# LinTempCont_indCh_proto.net
KiCad netlist of a schematic drawn in EAGLE
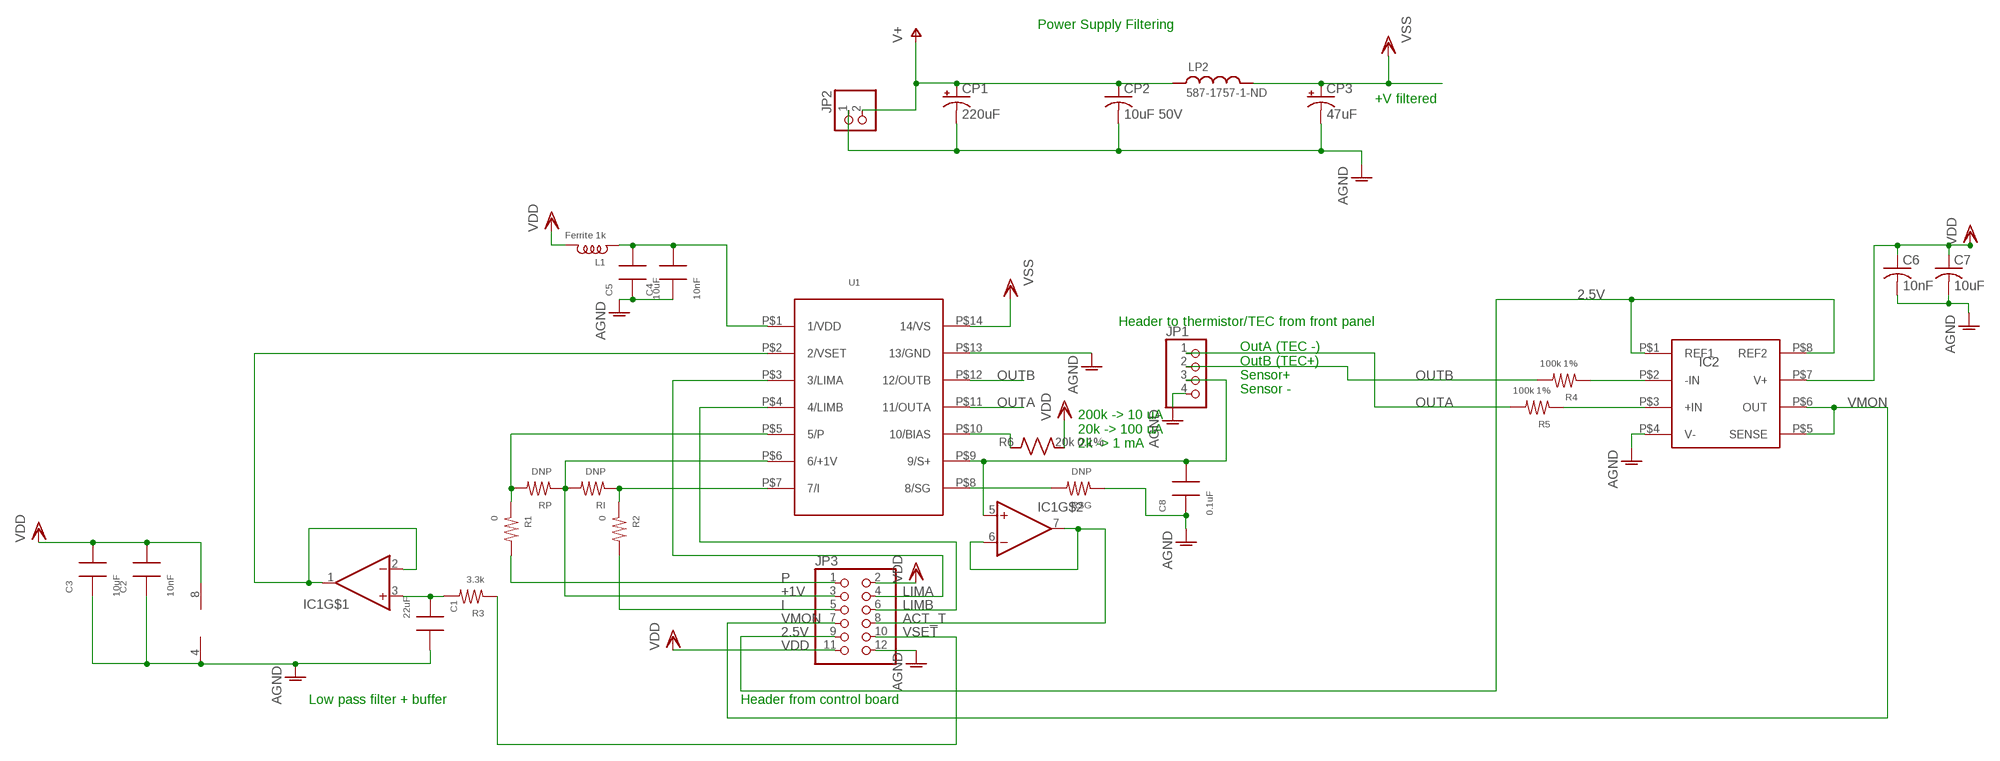
[diagram p0: schematic, sheet 1]

(export (version "E")
  (design (tool "Eeschema 10.0.6"))
  (components
    (comp (ref "C1")
      (value "22uF")
      (footprint "eagle-import:0805")
      (libsource (lib "eagle-import") (part "CAP0805"))
    )
    (comp (ref "C2")
      (value "10nF")
      (footprint "eagle-import:0603")
      (libsource (lib "eagle-import") (part "CAP0603"))
    )
    (comp (ref "C3")
      (value "10uF")
      (footprint "eagle-import:0805")
      (libsource (lib "eagle-import") (part "CAP0805"))
    )
    (comp (ref "C4")
      (value "10nF")
      (footprint "eagle-import:0805")
      (libsource (lib "eagle-import") (part "CAP0805"))
    )
    (comp (ref "C5")
      (value "10uF")
      (footprint "eagle-import:0603")
      (libsource (lib "eagle-import") (part "CAP0603"))
    )
    (comp (ref "C6")
      (value "10nF")
      (footprint "eagle-import:C0603")
      (libsource (lib "eagle-import") (part "C-USC0603"))
    )
    (comp (ref "C7")
      (value "10uF")
      (footprint "eagle-import:C0805")
      (libsource (lib "eagle-import") (part "C-USC0805"))
    )
    (comp (ref "C8")
      (value "0.1uF")
      (footprint "eagle-import:0603")
      (libsource (lib "eagle-import") (part "CAP0603"))
    )
    (comp (ref "CP1")
      (value "220uF")
      (footprint "eagle-import:PANASONIC_F")
      (libsource (lib "eagle-import") (part "CPOL-USF"))
    )
    (comp (ref "CP2")
      (value "10uF 50V")
      (footprint "eagle-import:C1206")
      (libsource (lib "eagle-import") (part "C-USC1206"))
    )
    (comp (ref "CP3")
      (value "47uF")
      (footprint "eagle-import:CT7343")
      (libsource (lib "eagle-import") (part "CPOL-USCT7343"))
    )
    (comp (ref "IC1")
      (value "OP727")
      (footprint "eagle-import:TSSOP8")
      (libsource (lib "eagle-import") (part "OP727"))
    )
    (comp (ref "IC2")
      (value "INA159")
      (footprint "eagle-import:VSSOP8")
      (libsource (lib "eagle-import") (part "INA159"))
    )
    (comp (ref "JP1")
      (value "SCRWTRM-1X4/90_ED550")
      (footprint "eagle-import:1X04_RA_SCRWTRM_ED550")
      (libsource (lib "eagle-import") (part "SCRWTRM-1X4/90_ED550"))
    )
    (comp (ref "JP2")
      (value "SCRWTRM-1X2/90_ED550")
      (footprint "eagle-import:1X02_RA_SCRWTRM_ED550")
      (libsource (lib "eagle-import") (part "SCRWTRM-1X2/90_ED550"))
    )
    (comp (ref "JP3")
      (value "PINHD-2X6")
      (footprint "eagle-import:2X06")
      (libsource (lib "eagle-import") (part "PINHD-2X6"))
    )
    (comp (ref "L1")
      (value "Ferrite 1k")
      (footprint "eagle-import:0805")
      (libsource (lib "eagle-import") (part "INDUCTOR-0805"))
    )
    (comp (ref "LP2")
      (value "587-1757-1-ND")
      (footprint "eagle-import:L_FERRITE_1810")
      (libsource (lib "eagle-import") (part "L_FERRITE_SMD"))
    )
    (comp (ref "R1")
      (value "0")
      (footprint "eagle-import:0603")
      (libsource (lib "eagle-import") (part "RES0603"))
    )
    (comp (ref "R2")
      (value "0")
      (footprint "eagle-import:0603")
      (libsource (lib "eagle-import") (part "RES0603"))
    )
    (comp (ref "R3")
      (value "3.3k")
      (footprint "eagle-import:0603")
      (libsource (lib "eagle-import") (part "RES0603"))
    )
    (comp (ref "R4")
      (value "100k 1%")
      (footprint "eagle-import:0603")
      (libsource (lib "eagle-import") (part "RES0603"))
    )
    (comp (ref "R5")
      (value "100k 1%")
      (footprint "eagle-import:0603")
      (libsource (lib "eagle-import") (part "RES0603"))
    )
    (comp (ref "R6")
      (value "20k 0.1%")
      (footprint "eagle-import:R_0805")
      (libsource (lib "eagle-import") (part "R_SMDR0805"))
    )
    (comp (ref "RI")
      (value "DNP")
      (footprint "eagle-import:0603")
      (libsource (lib "eagle-import") (part "RES0603"))
    )
    (comp (ref "RP")
      (value "DNP")
      (footprint "eagle-import:0603")
      (libsource (lib "eagle-import") (part "RES0603"))
    )
    (comp (ref "RSG")
      (value "DNP")
      (footprint "eagle-import:0603")
      (libsource (lib "eagle-import") (part "RES0603"))
    )
    (comp (ref "U1")
      (value "WTC3243")
      (footprint "eagle-import:WTC3293")
      (libsource (lib "eagle-import") (part "WTC3243"))
    )
  )
  (nets
    (net (code "1") (name "/+1V") (class "Default")
      (node (ref "JP3") (pin "3") (pinfunction "3_3") (pintype "passive"))
      (node (ref "RI") (pin "2") (pinfunction "P$2_2") (pintype "passive"))
      (node (ref "RP") (pin "1") (pinfunction "P$1_1") (pintype "passive"))
      (node (ref "U1") (pin "P$6") (pinfunction "6/+1V_P$6") (pintype "bidirectional"))
    )
    (net (code "2") (name "/2.5V") (class "Default")
      (node (ref "IC2") (pin "P$1") (pinfunction "REF1_P$1") (pintype "bidirectional"))
      (node (ref "IC2") (pin "P$8") (pinfunction "REF2_P$8") (pintype "bidirectional"))
      (node (ref "JP3") (pin "9") (pinfunction "9_9") (pintype "passive"))
    )
    (net (code "3") (name "/ACT_T") (class "Default")
      (node (ref "IC1") (pin "6") (pinfunction "-IN_6") (pintype "input"))
      (node (ref "IC1") (pin "7") (pinfunction "OUT_7") (pintype "output"))
      (node (ref "JP3") (pin "8") (pinfunction "8_8") (pintype "passive"))
    )
    (net (code "4") (name "/I") (class "Default")
      (node (ref "JP3") (pin "5") (pinfunction "5_5") (pintype "passive"))
      (node (ref "R2") (pin "2") (pinfunction "P$2_2") (pintype "passive"))
    )
    (net (code "5") (name "/LIMA") (class "Default")
      (node (ref "JP3") (pin "4") (pinfunction "4_4") (pintype "passive"))
      (node (ref "U1") (pin "P$3") (pinfunction "3/LIMA_P$3") (pintype "bidirectional"))
    )
    (net (code "6") (name "/LIMB") (class "Default")
      (node (ref "JP3") (pin "6") (pinfunction "6_6") (pintype "passive"))
      (node (ref "U1") (pin "P$4") (pinfunction "4/LIMB_P$4") (pintype "bidirectional"))
    )
    (net (code "7") (name "/OUTA") (class "Default")
      (node (ref "JP1") (pin "1") (pinfunction "1_1") (pintype "passive"))
      (node (ref "R5") (pin "2") (pinfunction "P$2_2") (pintype "passive"))
      (node (ref "U1") (pin "P$11") (pinfunction "11/OUTA_P$11") (pintype "bidirectional"))
    )
    (net (code "8") (name "/OUTB") (class "Default")
      (node (ref "JP1") (pin "2") (pinfunction "2_2") (pintype "passive"))
      (node (ref "R4") (pin "2") (pinfunction "P$2_2") (pintype "passive"))
      (node (ref "U1") (pin "P$12") (pinfunction "12/OUTB_P$12") (pintype "bidirectional"))
    )
    (net (code "9") (name "/P") (class "Default")
      (node (ref "JP3") (pin "1") (pinfunction "1_1") (pintype "passive"))
      (node (ref "R1") (pin "2") (pinfunction "P$2_2") (pintype "passive"))
    )
    (net (code "10") (name "/VMON") (class "Default")
      (node (ref "IC2") (pin "P$5") (pinfunction "SENSE_P$5") (pintype "bidirectional"))
      (node (ref "IC2") (pin "P$6") (pinfunction "OUT_P$6") (pintype "bidirectional"))
      (node (ref "JP3") (pin "7") (pinfunction "7_7") (pintype "passive"))
    )
    (net (code "11") (name "/VSET") (class "Default")
      (node (ref "JP3") (pin "10") (pinfunction "10_10") (pintype "passive"))
      (node (ref "R3") (pin "1") (pinfunction "P$1_1") (pintype "passive"))
    )
    (net (code "12") (name "AGND") (class "Default")
      (node (ref "C1") (pin "2") (pinfunction "P$2_2") (pintype "passive"))
      (node (ref "C2") (pin "1") (pinfunction "P$1_1") (pintype "passive"))
      (node (ref "C3") (pin "1") (pinfunction "P$1_1") (pintype "passive"))
      (node (ref "C4") (pin "1") (pinfunction "P$1_1") (pintype "passive"))
      (node (ref "C5") (pin "1") (pinfunction "P$1_1") (pintype "passive"))
      (node (ref "C6") (pin "2") (pinfunction "2_2") (pintype "passive"))
      (node (ref "C7") (pin "2") (pinfunction "2_2") (pintype "passive"))
      (node (ref "C8") (pin "1") (pinfunction "P$1_1") (pintype "passive"))
      (node (ref "CP1") (pin "-") (pinfunction "-_-") (pintype "passive"))
      (node (ref "CP2") (pin "2") (pinfunction "2_2") (pintype "passive"))
      (node (ref "CP3") (pin "-") (pinfunction "-_-") (pintype "passive"))
      (node (ref "IC1") (pin "4") (pinfunction "V-_4") (pintype "power_in"))
      (node (ref "IC2") (pin "P$4") (pinfunction "V-_P$4") (pintype "power_in"))
      (node (ref "JP1") (pin "4") (pinfunction "4_4") (pintype "passive"))
      (node (ref "JP2") (pin "1") (pinfunction "1_1") (pintype "passive"))
      (node (ref "JP3") (pin "12") (pinfunction "12_12") (pintype "passive"))
      (node (ref "RSG") (pin "1") (pinfunction "P$1_1") (pintype "passive"))
      (node (ref "U1") (pin "P$13") (pinfunction "13/GND_P$13") (pintype "power_in"))
    )
    (net (code "13") (name "Net-(C1-P$1)") (class "Default")
      (node (ref "C1") (pin "1") (pinfunction "P$1_1") (pintype "passive"))
      (node (ref "IC1") (pin "3") (pinfunction "+IN_3") (pintype "input"))
      (node (ref "R3") (pin "2") (pinfunction "P$2_2") (pintype "passive"))
    )
    (net (code "14") (name "Net-(C4-P$2)") (class "Default")
      (node (ref "C4") (pin "2") (pinfunction "P$2_2") (pintype "passive"))
      (node (ref "C5") (pin "2") (pinfunction "P$2_2") (pintype "passive"))
      (node (ref "L1") (pin "1") (pinfunction "P$1_1") (pintype "passive"))
      (node (ref "U1") (pin "P$1") (pinfunction "1/VDD_P$1") (pintype "power_in"))
    )
    (net (code "15") (name "Net-(C8-P$2)") (class "Default")
      (node (ref "C8") (pin "2") (pinfunction "P$2_2") (pintype "passive"))
      (node (ref "IC1") (pin "5") (pinfunction "+IN_5") (pintype "input"))
      (node (ref "JP1") (pin "3") (pinfunction "3_3") (pintype "passive"))
      (node (ref "U1") (pin "P$9") (pinfunction "9/S+_P$9") (pintype "bidirectional"))
    )
    (net (code "16") (name "Net-(IC1A--IN)") (class "Default")
      (node (ref "IC1") (pin "1") (pinfunction "OUT_1") (pintype "output"))
      (node (ref "IC1") (pin "2") (pinfunction "-IN_2") (pintype "input"))
      (node (ref "U1") (pin "P$2") (pinfunction "2/VSET_P$2") (pintype "input"))
    )
    (net (code "17") (name "Net-(IC2-+IN)") (class "Default")
      (node (ref "IC2") (pin "P$3") (pinfunction "+IN_P$3") (pintype "bidirectional"))
      (node (ref "R5") (pin "1") (pinfunction "P$1_1") (pintype "passive"))
    )
    (net (code "18") (name "Net-(IC2--IN)") (class "Default")
      (node (ref "IC2") (pin "P$2") (pinfunction "-IN_P$2") (pintype "bidirectional"))
      (node (ref "R4") (pin "1") (pinfunction "P$1_1") (pintype "passive"))
    )
    (net (code "19") (name "Net-(R1-P$1)") (class "Default")
      (node (ref "R1") (pin "1") (pinfunction "P$1_1") (pintype "passive"))
      (node (ref "RP") (pin "2") (pinfunction "P$2_2") (pintype "passive"))
      (node (ref "U1") (pin "P$5") (pinfunction "5/P_P$5") (pintype "bidirectional"))
    )
    (net (code "20") (name "Net-(R2-P$1)") (class "Default")
      (node (ref "R2") (pin "1") (pinfunction "P$1_1") (pintype "passive"))
      (node (ref "RI") (pin "1") (pinfunction "P$1_1") (pintype "passive"))
      (node (ref "U1") (pin "P$7") (pinfunction "7/I_P$7") (pintype "bidirectional"))
    )
    (net (code "21") (name "Net-(R6-1)") (class "Default")
      (node (ref "R6") (pin "P$1") (pinfunction "1_P$1") (pintype "passive"))
      (node (ref "U1") (pin "P$10") (pinfunction "10/BIAS_P$10") (pintype "bidirectional"))
    )
    (net (code "22") (name "Net-(RSG-P$2)") (class "Default")
      (node (ref "RSG") (pin "2") (pinfunction "P$2_2") (pintype "passive"))
      (node (ref "U1") (pin "P$8") (pinfunction "8/SG_P$8") (pintype "bidirectional"))
    )
    (net (code "23") (name "V+") (class "Default")
      (node (ref "CP1") (pin "+") (pinfunction "+_+") (pintype "passive"))
      (node (ref "CP2") (pin "1") (pinfunction "1_1") (pintype "passive"))
      (node (ref "JP2") (pin "2") (pinfunction "2_2") (pintype "passive"))
      (node (ref "LP2") (pin "P$1") (pinfunction "1_P$1") (pintype "passive"))
    )
    (net (code "24") (name "VDD") (class "Default")
      (node (ref "C2") (pin "2") (pinfunction "P$2_2") (pintype "passive"))
      (node (ref "C3") (pin "2") (pinfunction "P$2_2") (pintype "passive"))
      (node (ref "C6") (pin "1") (pinfunction "1_1") (pintype "passive"))
      (node (ref "C7") (pin "1") (pinfunction "1_1") (pintype "passive"))
      (node (ref "IC1") (pin "8") (pinfunction "V+_8") (pintype "power_in"))
      (node (ref "IC2") (pin "P$7") (pinfunction "V+_P$7") (pintype "power_in"))
      (node (ref "JP3") (pin "11") (pinfunction "11_11") (pintype "passive"))
      (node (ref "JP3") (pin "2") (pinfunction "2_2") (pintype "passive"))
      (node (ref "L1") (pin "2") (pinfunction "P$2_2") (pintype "passive"))
      (node (ref "R6") (pin "P$2") (pinfunction "2_P$2") (pintype "passive"))
    )
    (net (code "25") (name "VSS") (class "Default")
      (node (ref "CP3") (pin "+") (pinfunction "+_+") (pintype "passive"))
      (node (ref "LP2") (pin "P$2") (pinfunction "2_P$2") (pintype "passive"))
      (node (ref "U1") (pin "P$14") (pinfunction "14/VS_P$14") (pintype "power_in"))
    )
  )
)
